# Wemos_Board.net
KiCad netlist of a schematic drawn in EasyEDA Pro
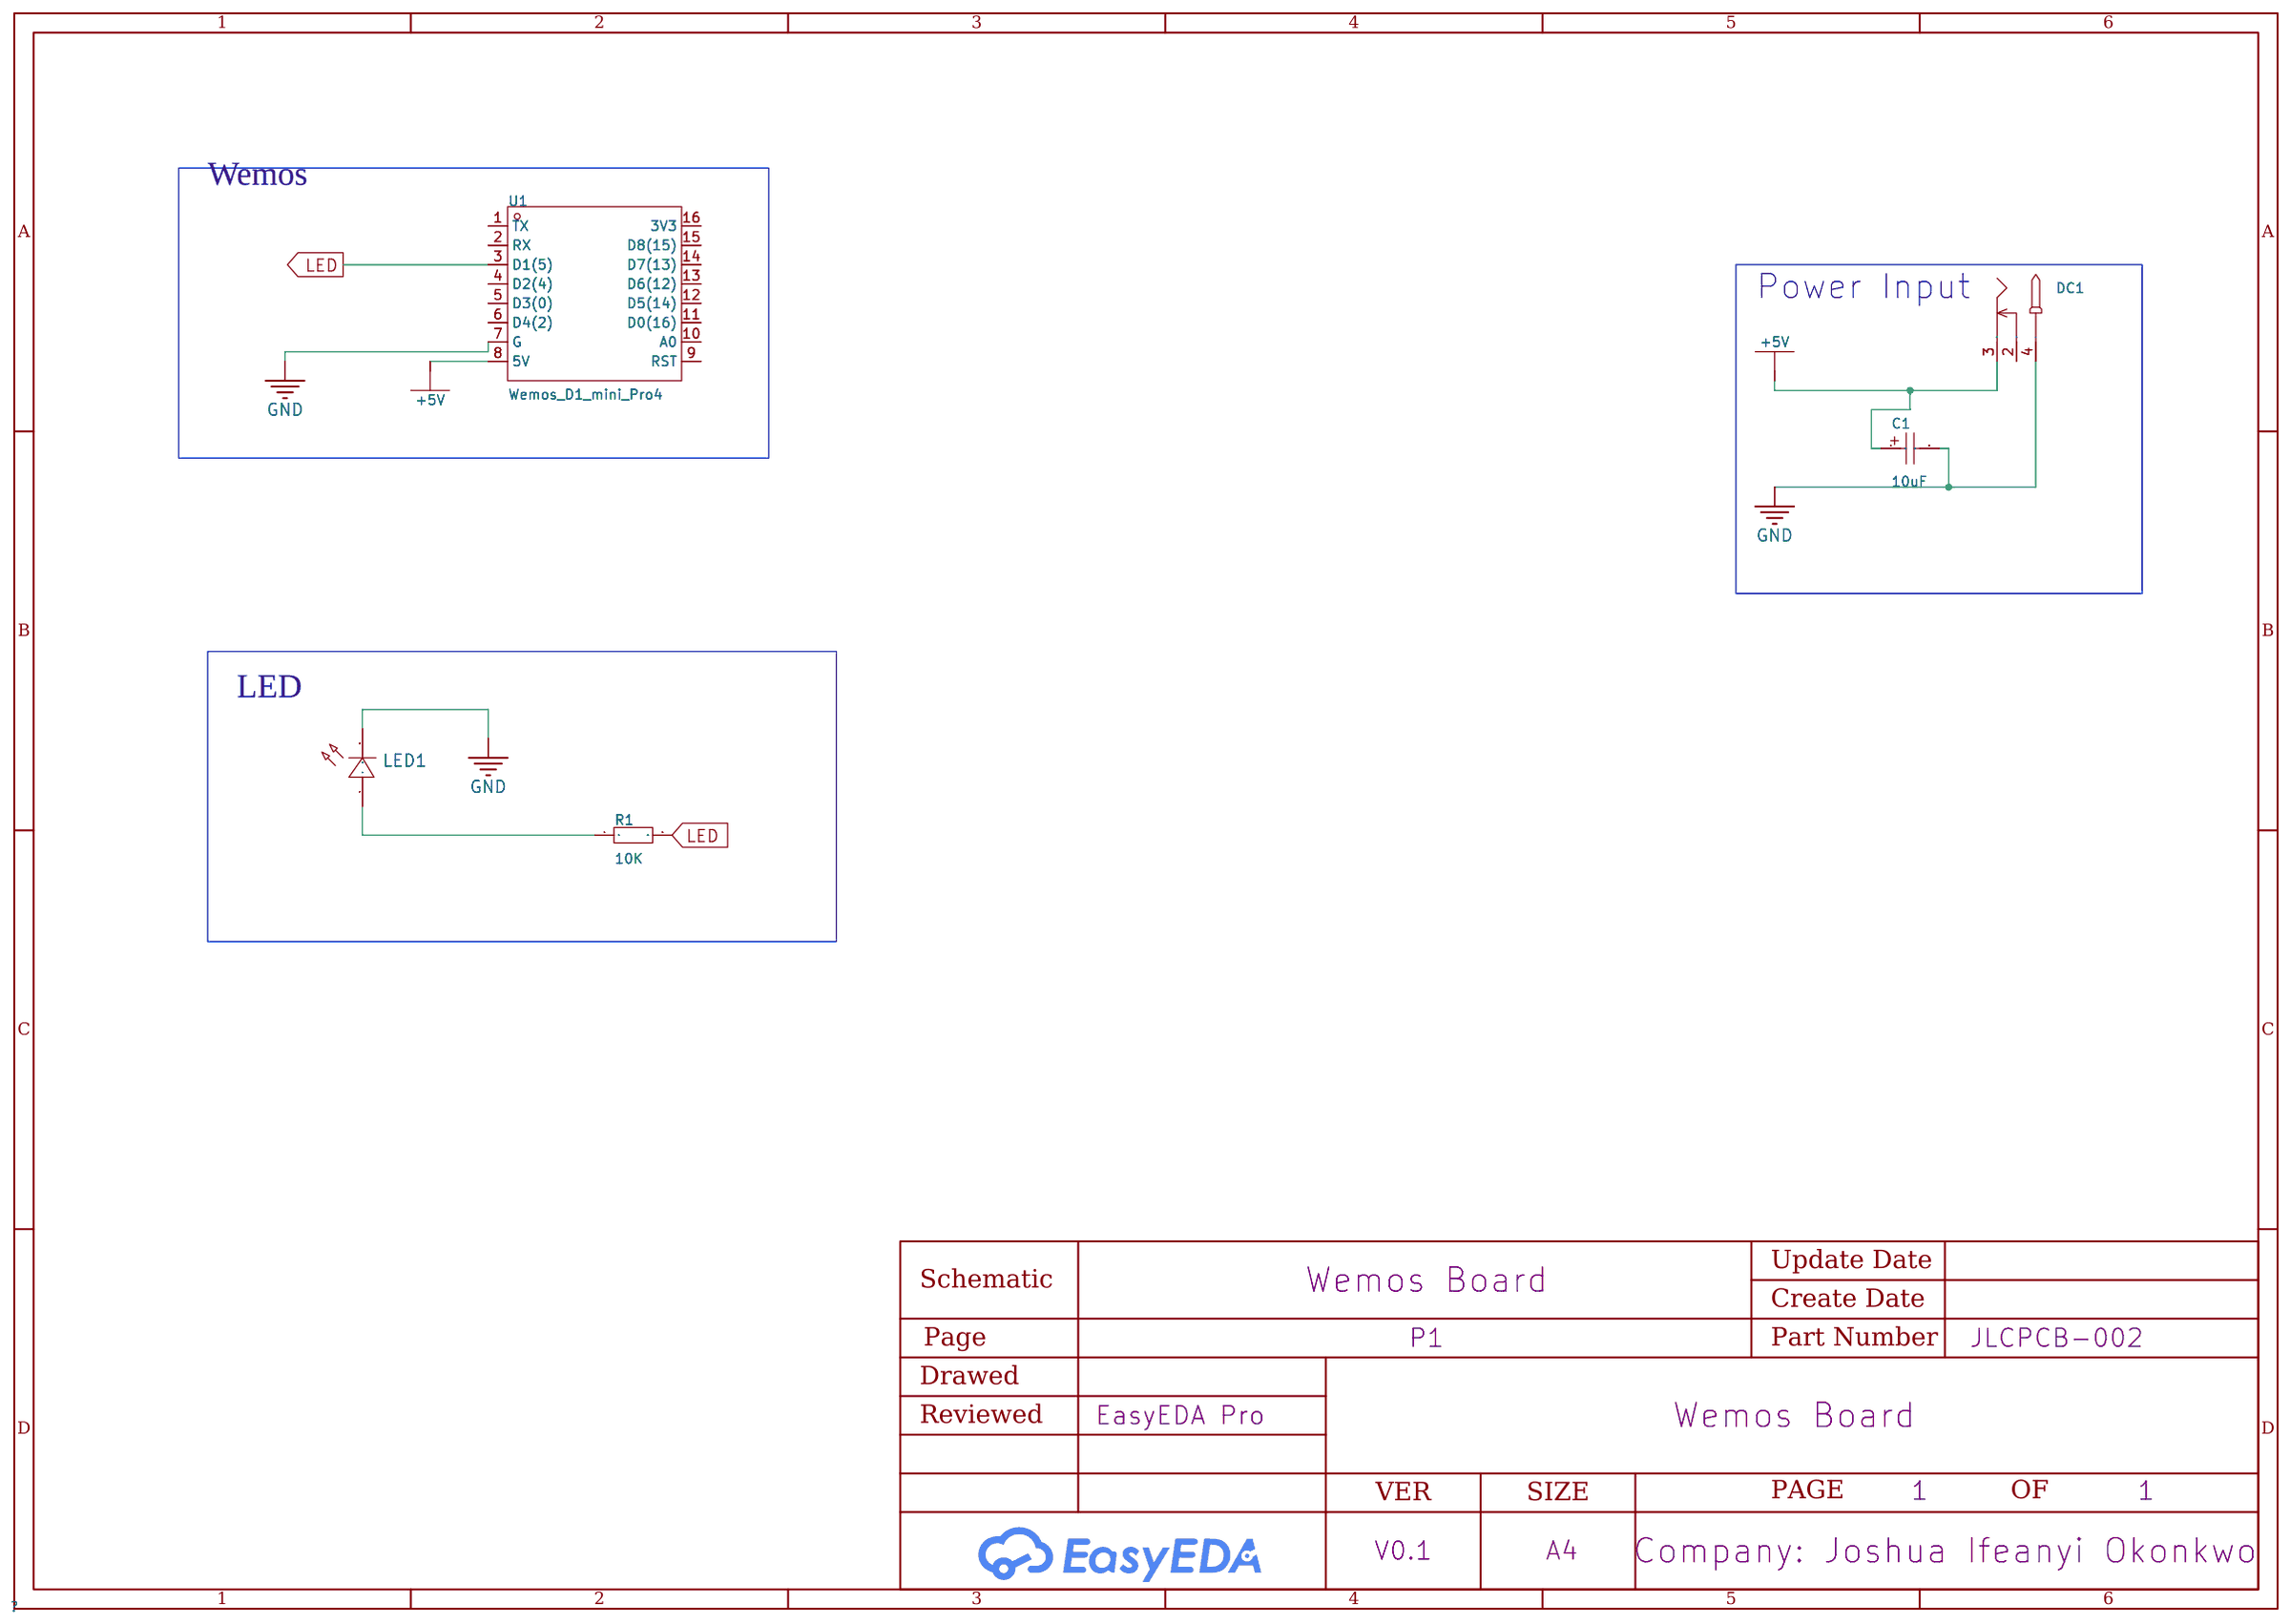
[diagram p0: schematic sheet]

(export (version "E")
  (design (tool "Eeschema 10.0.6"))
  (components
    (comp (ref "C1")
      (value "10uF")
      (footprint "easyedapro:CAP-SMD_BD3.0-L3.3-W3.3-RD")
      (libsource (lib "easyedapro") (part "C_Ele_SMD"))
    )
    (comp (ref "DC1")
      (value "~")
      (footprint "easyedapro:DC-IN-TH_DC-5520-1")
      (libsource (lib "easyedapro") (part "DC电源接口"))
    )
    (comp (ref "LED1")
      (value "~")
      (footprint "easyedapro:LED0402-RD_YELLOW")
      (libsource (lib "easyedapro") (part "LED_R"))
    )
    (comp (ref "R1") (value "10K") (footprint "easyedapro:R0201") (libsource (lib "easyedapro") (part "Res")))
    (comp (ref "U1")
      (value "Wemos_D1_mini_Pro4")
      (footprint "easyedapro:DIP-16_WEMOS_D1_MINI_PRO4")
      (libsource (lib "easyedapro") (part "WEMOS_D1_MINI_PRO4"))
    )
  )
  (nets
    (net (code "1") (name "+5V") (class "Default")
      (node (ref "C1") (pin "1") (pinfunction "1_1") (pintype "input"))
      (node (ref "DC1") (pin "3") (pinfunction "3_3") (pintype "input"))
      (node (ref "U1") (pin "8") (pinfunction "5V_8") (pintype "input"))
    )
    (net (code "2") (name "GND") (class "Default")
      (node (ref "C1") (pin "2") (pinfunction "2_2") (pintype "input"))
      (node (ref "DC1") (pin "4") (pinfunction "4_4") (pintype "input"))
      (node (ref "LED1") (pin "2") (pinfunction "C_2") (pintype "input"))
      (node (ref "U1") (pin "7") (pinfunction "G_7") (pintype "input"))
    )
    (net (code "3") (name "LED") (class "Default")
      (node (ref "R1") (pin "2") (pinfunction "2_2") (pintype "input"))
      (node (ref "U1") (pin "3") (pinfunction "D1(5)_3") (pintype "input"))
    )
    (net (code "4") (name "Net-(LED1-A)") (class "Default")
      (node (ref "LED1") (pin "1") (pinfunction "A_1") (pintype "input"))
      (node (ref "R1") (pin "1") (pinfunction "1_1") (pintype "input"))
    )
    (net (code "5") (name "unconnected-(DC1-Pad2)") (class "Default")
      (node (ref "DC1") (pin "2") (pinfunction "2_2") (pintype "input"))
    )
    (net (code "6") (name "unconnected-(U1-3V3-Pad16)") (class "Default")
      (node (ref "U1") (pin "16") (pinfunction "3V3_16") (pintype "input"))
    )
    (net (code "7") (name "unconnected-(U1-A0-Pad10)") (class "Default")
      (node (ref "U1") (pin "10") (pinfunction "A0_10") (pintype "input"))
    )
    (net (code "8") (name "unconnected-(U1-D0(16)-Pad11)") (class "Default")
      (node (ref "U1") (pin "11") (pinfunction "D0(16)_11") (pintype "input"))
    )
    (net (code "9") (name "unconnected-(U1-D2(4)-Pad4)") (class "Default")
      (node (ref "U1") (pin "4") (pinfunction "D2(4)_4") (pintype "input"))
    )
    (net (code "10") (name "unconnected-(U1-D3(0)-Pad5)") (class "Default")
      (node (ref "U1") (pin "5") (pinfunction "D3(0)_5") (pintype "input"))
    )
    (net (code "11") (name "unconnected-(U1-D4(2)-Pad6)") (class "Default")
      (node (ref "U1") (pin "6") (pinfunction "D4(2)_6") (pintype "input"))
    )
    (net (code "12") (name "unconnected-(U1-D5(14)-Pad12)") (class "Default")
      (node (ref "U1") (pin "12") (pinfunction "D5(14)_12") (pintype "input"))
    )
    (net (code "13") (name "unconnected-(U1-D6(12)-Pad13)") (class "Default")
      (node (ref "U1") (pin "13") (pinfunction "D6(12)_13") (pintype "input"))
    )
    (net (code "14") (name "unconnected-(U1-D7(13)-Pad14)") (class "Default")
      (node (ref "U1") (pin "14") (pinfunction "D7(13)_14") (pintype "input"))
    )
    (net (code "15") (name "unconnected-(U1-D8(15)-Pad15)") (class "Default")
      (node (ref "U1") (pin "15") (pinfunction "D8(15)_15") (pintype "input"))
    )
    (net (code "16") (name "unconnected-(U1-RST-Pad9)") (class "Default")
      (node (ref "U1") (pin "9") (pinfunction "RST_9") (pintype "input"))
    )
    (net (code "17") (name "unconnected-(U1-RX-Pad2)") (class "Default")
      (node (ref "U1") (pin "2") (pinfunction "RX_2") (pintype "input"))
    )
    (net (code "18") (name "unconnected-(U1-TX-Pad1)") (class "Default")
      (node (ref "U1") (pin "1") (pinfunction "TX_1") (pintype "input"))
    )
  )
)
